# SW6124Demo_board.net
KiCad netlist of a schematic drawn in Altium Designer
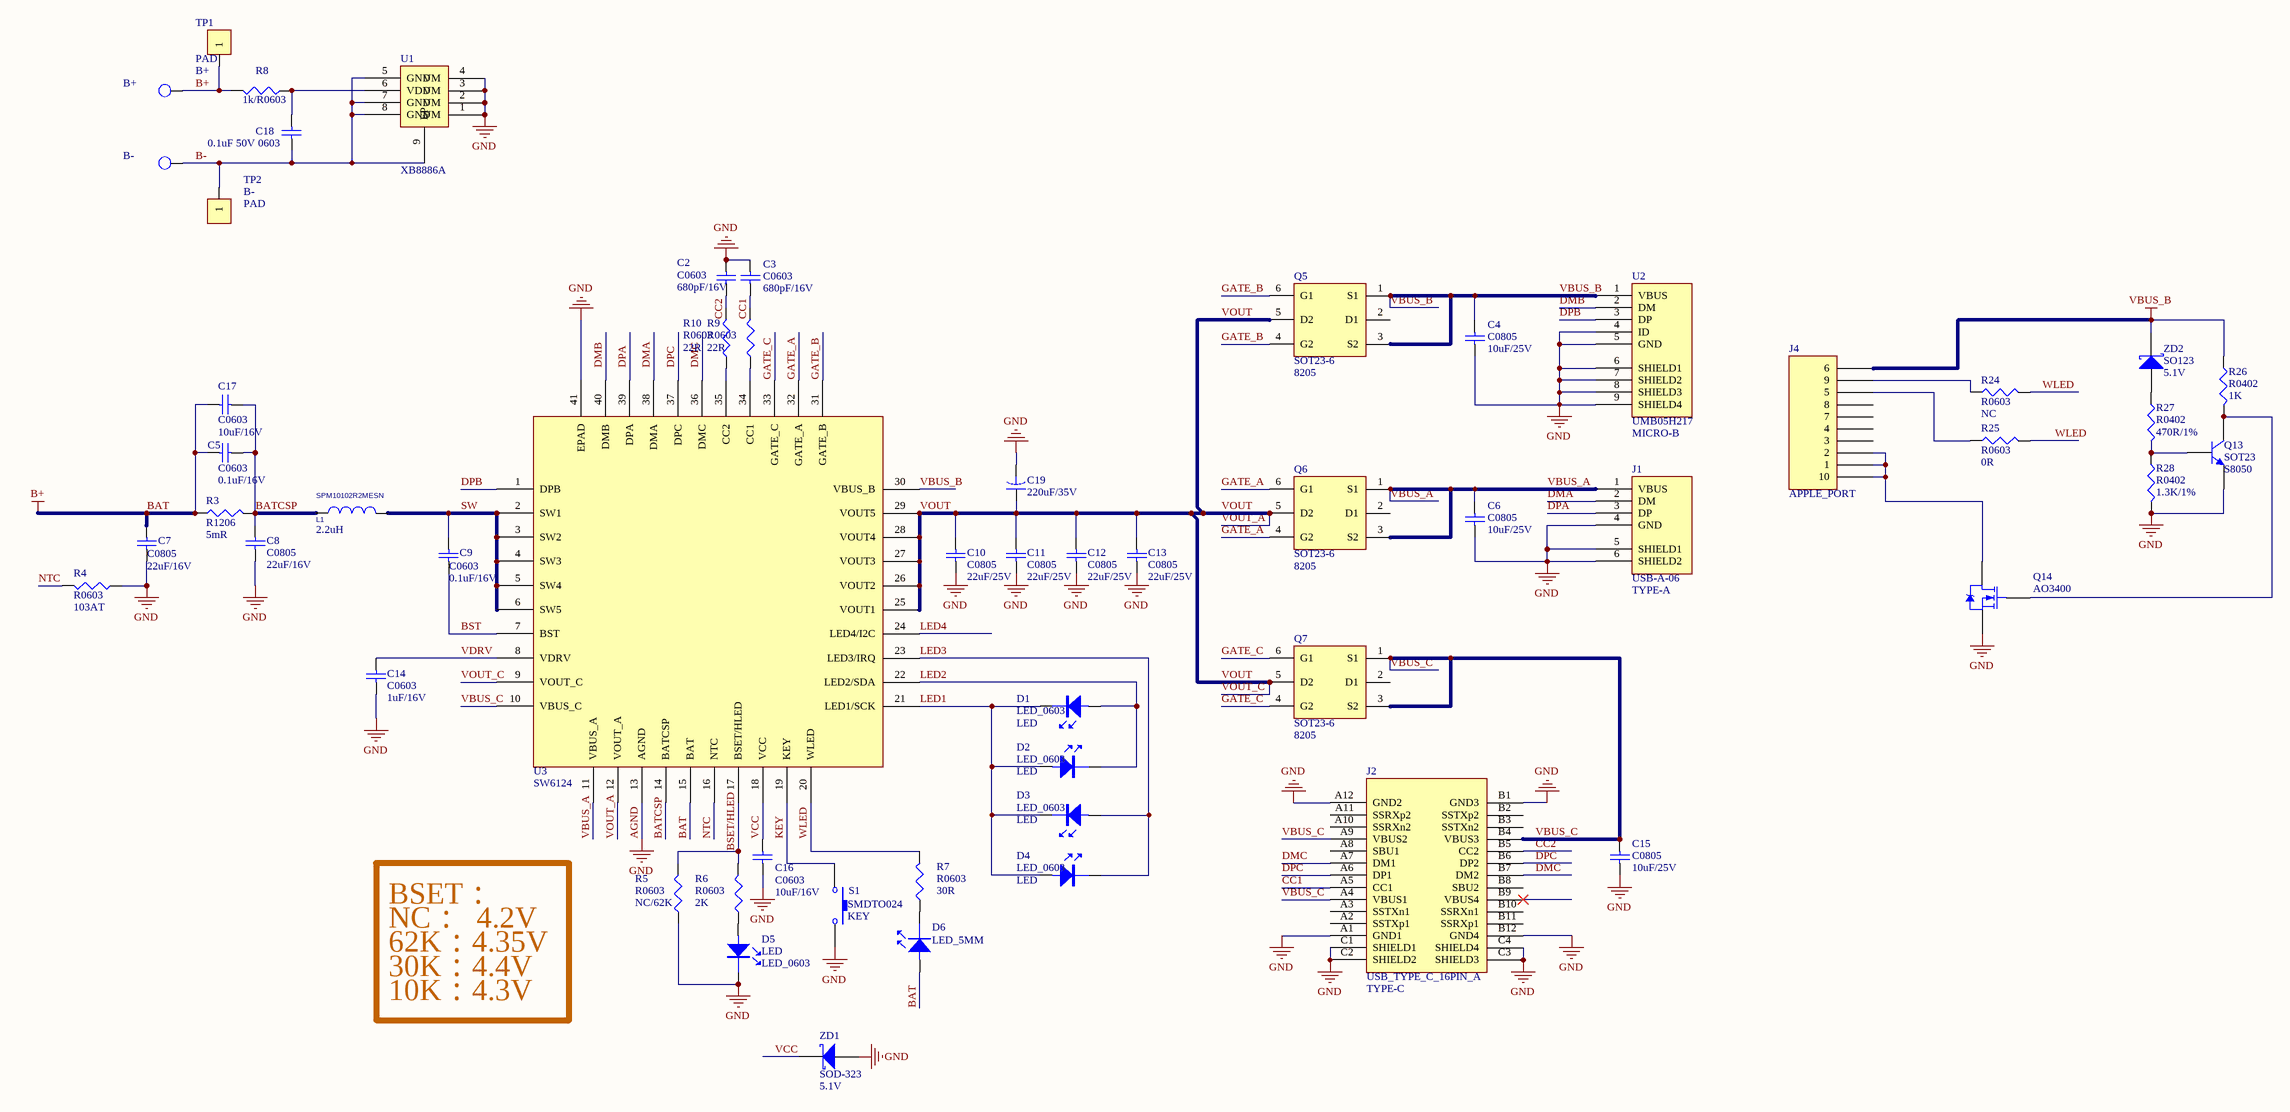
[diagram p0: SW6124Demo board.SchDoc]

(export (version "E")
  (design (tool "Eeschema 10.0.6"))
  (components
    (comp (ref "B+") (value "PDA") (footprint "PAD") (libsource (lib "ZYX") (part "PDA")))
    (comp (ref "B-") (value "PDA") (footprint "PAD") (libsource (lib "ZYX") (part "PDA")))
    (comp (ref "C2")
      (value "C0603")
      (footprint "C0603")
      (description "Capacitor")
      (fields (field (name "ALTIUM_VALUE") "680pF/16V") (field (name "PUBLISHER") "Altium Limited"))
      (libsource (lib "*") (part "CAP0603"))
    )
    (comp (ref "C3")
      (value "C0603")
      (footprint "C0603")
      (description "Capacitor")
      (fields (field (name "ALTIUM_VALUE") "680pF/16V") (field (name "PUBLISHER") "Altium Limited"))
      (libsource (lib "*") (part "CAP0603"))
    )
    (comp (ref "C4")
      (value "C0805")
      (footprint "C0805")
      (description "Capacitor")
      (fields (field (name "ALTIUM_VALUE") "10uF/25V") (field (name "PUBLISHER") "Altium Limited"))
      (libsource (lib "*") (part "CAP0603"))
    )
    (comp (ref "C5")
      (value "C0603")
      (footprint "C0603")
      (description "Capacitor")
      (fields (field (name "ALTIUM_VALUE") "0.1uF/16V") (field (name "PUBLISHER") "Altium Limited"))
      (libsource (lib "*") (part "CAP0603"))
    )
    (comp (ref "C6")
      (value "C0805")
      (footprint "C0805")
      (description "Capacitor")
      (fields (field (name "ALTIUM_VALUE") "10uF/25V") (field (name "PUBLISHER") "Altium Limited"))
      (libsource (lib "*") (part "CAP0603"))
    )
    (comp (ref "C7")
      (value "C0805")
      (footprint "C0805")
      (description "Capacitor")
      (fields (field (name "ALTIUM_VALUE") "22uF/16V") (field (name "PUBLISHER") "Altium Limited"))
      (libsource (lib "*") (part "CAP0805"))
    )
    (comp (ref "C8")
      (value "C0805")
      (footprint "C0805")
      (description "Capacitor")
      (fields (field (name "ALTIUM_VALUE") "22uF/16V") (field (name "PUBLISHER") "Altium Limited"))
      (libsource (lib "*") (part "CAP0805"))
    )
    (comp (ref "C9")
      (value "C0603")
      (footprint "C0603")
      (description "Capacitor")
      (fields (field (name "ALTIUM_VALUE") "0.1uF/16V") (field (name "PUBLISHER") "Altium Limited"))
      (libsource (lib "*") (part "CAP0603"))
    )
    (comp (ref "C10")
      (value "C0805")
      (footprint "C0805")
      (description "Capacitor")
      (fields (field (name "ALTIUM_VALUE") "22uF/25V") (field (name "PUBLISHER") "Altium Limited"))
      (libsource (lib "*") (part "CAP0805"))
    )
    (comp (ref "C11")
      (value "C0805")
      (footprint "C0805")
      (description "Capacitor")
      (fields (field (name "ALTIUM_VALUE") "22uF/25V") (field (name "PUBLISHER") "Altium Limited"))
      (libsource (lib "*") (part "CAP0805"))
    )
    (comp (ref "C12")
      (value "C0805")
      (footprint "C0805")
      (description "Capacitor")
      (fields (field (name "ALTIUM_VALUE") "22uF/25V") (field (name "PUBLISHER") "Altium Limited"))
      (libsource (lib "*") (part "CAP0805"))
    )
    (comp (ref "C13")
      (value "C0805")
      (footprint "C0805")
      (description "Capacitor")
      (fields (field (name "ALTIUM_VALUE") "22uF/25V") (field (name "PUBLISHER") "Altium Limited"))
      (libsource (lib "*") (part "CAP0805"))
    )
    (comp (ref "C14")
      (value "C0603")
      (footprint "C0603")
      (description "Capacitor")
      (fields (field (name "ALTIUM_VALUE") "1uF/16V") (field (name "PUBLISHER") "Altium Limited"))
      (libsource (lib "*") (part "CAP0603"))
    )
    (comp (ref "C15")
      (value "C0805")
      (footprint "C0805")
      (description "Capacitor")
      (fields (field (name "ALTIUM_VALUE") "10uF/25V") (field (name "PUBLISHER") "Altium Limited"))
      (libsource (lib "*") (part "CAP0603"))
    )
    (comp (ref "C16")
      (value "C0603")
      (footprint "C0603")
      (description "Capacitor")
      (fields (field (name "ALTIUM_VALUE") "10uF/16V") (field (name "PUBLISHER") "Altium Limited"))
      (libsource (lib "*") (part "CAP0603"))
    )
    (comp (ref "C17")
      (value "C0603")
      (footprint "C0603")
      (description "Capacitor")
      (fields (field (name "ALTIUM_VALUE") "10uF/16V") (field (name "PUBLISHER") "Altium Limited"))
      (libsource (lib "*") (part "CAP0603"))
    )
    (comp (ref "C18") (value "0.1uF 50V 0603") (footprint "LIB:C0402") (libsource (lib "ZYX") (part "Cap")))
    (comp (ref "C19")
      (value "220uF/35V")
      (footprint "Cap  ( E )  6.5 * 12.0  Erect")
      (description "Electroytic Capacitor, 100uF/35V, ±20%, 105℃，Φ 6.5 * 12.0 mm")
      (fields (field (name "Comment") "E - Cap") (field (name "PUBLISHER") "Altium Limited"))
      (libsource (lib "D-lib") (part "E - Cap"))
    )
    (comp (ref "D1") (value "LED") (footprint "LED_0603") (libsource (lib "*") (part "LED")))
    (comp (ref "D2") (value "LED") (footprint "LED_0603") (libsource (lib "*") (part "LED")))
    (comp (ref "D3") (value "LED") (footprint "LED_0603") (libsource (lib "*") (part "LED")))
    (comp (ref "D4") (value "LED") (footprint "LED_0603") (libsource (lib "*") (part "LED")))
    (comp (ref "D5") (value "LED") (footprint "LED_0603") (libsource (lib "*") (part "LED")))
    (comp (ref "D6")
      (value "LED_5MM")
      (footprint "LED_5MM")
      (fields (field (name "FOOTPRINF") "LED_5MM"))
      (libsource (lib "*") (part "LED"))
    )
    (comp (ref "J1")
      (value "TYPE-A")
      (footprint "USB-A-06")
      (fields (field (name "FOOTPRINF") "USB-A-06") (field (name "Comment") "TYPE-A-1"))
      (libsource (lib "*") (part "TYPE-A-1"))
    )
    (comp (ref "J2") (value "TYPE-C") (footprint "USB_TYPE_C_16PIN_A") (libsource (lib "*") (part "TYPE-C")))
    (comp (ref "J4")
      (value "APPLE_PORT")
      (footprint "Lightning")
      (libsource (lib "TEST") (part "APPLE_PORT"))
    )
    (comp (ref "L1")
      (value "SPM10102R2MESN")
      (footprint "INDUCTOR_SPM1010")
      (fields (field (name "ALTIUM_VALUE") "2.2uH"))
      (libsource (lib "*") (part "INDUCTOR"))
    )
    (comp (ref "Q5")
      (value "8205")
      (footprint "SOT23-6")
      (fields (field (name "FOOTPRINF") "SOT23-6"))
      (libsource (lib "*") (part "8205B"))
    )
    (comp (ref "Q6")
      (value "8205")
      (footprint "SOT23-6")
      (fields (field (name "FOOTPRINF") "SOT23-6"))
      (libsource (lib "*") (part "8205B"))
    )
    (comp (ref "Q7")
      (value "8205")
      (footprint "SOT23-6")
      (fields (field (name "FOOTPRINF") "SOT23-6"))
      (libsource (lib "*") (part "8205B"))
    )
    (comp (ref "Q13")
      (value "S8050")
      (footprint "SOT23")
      (description "NPN General Purpose Amplifier")
      (fields (field (name "PUBLISHER") "Altium Limited"))
      (libsource (lib "Miscellaneous Devices") (part "2N3904"))
    )
    (comp (ref "Q14")
      (value "AO3400")
      (footprint "SOT-23-3")
      (description "N-Channel Power MOSFET")
      (fields (field (name "Comment") "NMOS-2") (field (name "PUBLISHER") "Altium Limited"))
      (libsource (lib "D-lib") (part "NMOS-2"))
    )
    (comp (ref "R3")
      (value "R1206")
      (footprint "R1206")
      (description "Resistor")
      (fields (field (name "ALTIUM_VALUE") "5mR") (field (name "PUBLISHER") "Altium Limited"))
      (libsource (lib "*") (part "RES"))
    )
    (comp (ref "R4")
      (value "R0603")
      (footprint "R0603")
      (description "Resistor")
      (fields (field (name "ALTIUM_VALUE") "103AT") (field (name "PUBLISHER") "Altium Limited"))
      (libsource (lib "*") (part "RES"))
    )
    (comp (ref "R5")
      (value "R0603")
      (footprint "R0603")
      (description "Resistor")
      (fields (field (name "ALTIUM_VALUE") "NC/62K") (field (name "PUBLISHER") "Altium Limited"))
      (libsource (lib "*") (part "RES"))
    )
    (comp (ref "R6")
      (value "R0603")
      (footprint "R0603")
      (description "Resistor")
      (fields (field (name "ALTIUM_VALUE") "2K") (field (name "PUBLISHER") "Altium Limited"))
      (libsource (lib "*") (part "RES"))
    )
    (comp (ref "R7")
      (value "R0603")
      (footprint "R0603")
      (description "Resistor")
      (fields (field (name "ALTIUM_VALUE") "30R") (field (name "PUBLISHER") "Altium Limited"))
      (libsource (lib "*") (part "RES"))
    )
    (comp (ref "R8")
      (value "1k/R0603")
      (footprint "R0402")
      (description "Resistor")
      (fields (field (name "PUBLISHER") "Altium Limited"))
      (libsource (lib "*") (part "RES"))
    )
    (comp (ref "R9")
      (value "R0603")
      (footprint "R0603")
      (description "Resistor")
      (fields (field (name "ALTIUM_VALUE") "22R") (field (name "PUBLISHER") "Altium Limited"))
      (libsource (lib "*") (part "RES"))
    )
    (comp (ref "R10")
      (value "R0603")
      (footprint "R0603")
      (description "Resistor")
      (fields (field (name "ALTIUM_VALUE") "22R") (field (name "PUBLISHER") "Altium Limited"))
      (libsource (lib "*") (part "RES"))
    )
    (comp (ref "R24")
      (value "R0603")
      (footprint "R0402")
      (description "Resistor")
      (fields (field (name "ALTIUM_VALUE") "NC") (field (name "PUBLISHER") "Altium Limited"))
      (libsource (lib "*") (part "RES"))
    )
    (comp (ref "R25")
      (value "R0603")
      (footprint "R0402")
      (description "Resistor")
      (fields (field (name "ALTIUM_VALUE") "0R") (field (name "PUBLISHER") "Altium Limited"))
      (libsource (lib "*") (part "RES"))
    )
    (comp (ref "R26")
      (value "R0402")
      (footprint "R0402")
      (description "Resistor")
      (fields (field (name "ALTIUM_VALUE") "1K") (field (name "PUBLISHER") "Altium Limited"))
      (libsource (lib "Miscellaneous Devices") (part "Res3"))
    )
    (comp (ref "R27")
      (value "R0402")
      (footprint "R0402")
      (description "Resistor")
      (fields (field (name "ALTIUM_VALUE") "470R/1%") (field (name "PUBLISHER") "Altium Limited"))
      (libsource (lib "Miscellaneous Devices") (part "Res3"))
    )
    (comp (ref "R28")
      (value "R0402")
      (footprint "R0402")
      (description "Resistor")
      (fields (field (name "ALTIUM_VALUE") "1.3K/1%") (field (name "PUBLISHER") "Altium Limited"))
      (libsource (lib "Miscellaneous Devices") (part "Res3"))
    )
    (comp (ref "S1")
      (value "KEY")
      (footprint "SMDTO024")
      (fields (field (name "FOOTPRINF") "SMDTO024"))
      (libsource (lib "*") (part "SW K"))
    )
    (comp (ref "TP1") (value "B+") (footprint "PAD") (libsource (lib "*") (part "Test Point")))
    (comp (ref "TP2") (value "B-") (footprint "PAD") (libsource (lib "") (part "Test Point_1")))
    (comp (ref "U1") (value "XB8886A") (footprint "SOP-8-G") (libsource (lib "ZYX") (part "XB8089")))
    (comp (ref "U2")
      (value "MICRO-B")
      (footprint "UMB05H217")
      (fields (field (name "FOOTPRINTF") "UMB05H217") (field (name "Comment") "USB_MICRO_B"))
      (libsource (lib "*") (part "USB_MICRO_B"))
    )
    (comp (ref "U3")
      (value "SW6124")
      (footprint "QFN40_EPAD_SW6124_6X6")
      (libsource (lib "*") (part "SW6124"))
    )
    (comp (ref "ZD1")
      (value "SOD-323")
      (footprint "SOD-123")
      (description "Schottky Rectifier")
      (fields (field (name "ALTIUM_UNNAMED_1") "5.1V") (field (name "PUBLISHER") "Altium Limited"))
      (libsource (lib "Miscellaneous Devices") (part "Diode 11DQ03"))
    )
    (comp (ref "ZD2")
      (value "5.1V")
      (footprint "SO123")
      (description "Schottky Rectifier")
      (fields (field (name "PUBLISHER") "Altium Limited"))
      (libsource (lib "Miscellaneous Devices") (part "Diode 10TQ035"))
    )
  )
  (nets
    (net (code "1") (name "/B-") (class "Default")
      (node (ref "B-") (pin "0") (pintype "passive"))
      (node (ref "C18") (pin "1") (pinfunction "1_1") (pintype "passive"))
      (node (ref "TP2") (pin "1") (pinfunction "1_1") (pintype "passive"))
      (node (ref "U1") (pin "5") (pinfunction "GND_5") (pintype "passive"))
      (node (ref "U1") (pin "7") (pinfunction "GND_7") (pintype "passive"))
      (node (ref "U1") (pin "8") (pinfunction "GND_8") (pintype "passive"))
      (node (ref "U1") (pin "9") (pinfunction "EP_9") (pintype "passive"))
    )
    (net (code "2") (name "/BATCSP") (class "Default")
      (node (ref "C17") (pin "1") (pinfunction "1_1") (pintype "passive"))
      (node (ref "C5") (pin "2") (pinfunction "2_2") (pintype "passive"))
      (node (ref "C8") (pin "2") (pinfunction "2_2") (pintype "passive"))
      (node (ref "L1") (pin "1") (pinfunction "1_1") (pintype "passive"))
      (node (ref "R3") (pin "2") (pinfunction "2_2") (pintype "passive"))
      (node (ref "U3") (pin "14") (pinfunction "BATCSP_14") (pintype "passive"))
    )
    (net (code "3") (name "/BSET{slash}HLED") (class "Default")
      (node (ref "R5") (pin "2") (pinfunction "2_2") (pintype "passive"))
      (node (ref "R6") (pin "2") (pinfunction "2_2") (pintype "passive"))
      (node (ref "U3") (pin "17") (pinfunction "BSET/HLED_17") (pintype "passive"))
    )
    (net (code "4") (name "/BST") (class "Default")
      (node (ref "C9") (pin "1") (pinfunction "1_1") (pintype "passive"))
      (node (ref "U3") (pin "7") (pinfunction "BST_7") (pintype "passive"))
    )
    (net (code "5") (name "/CC1") (class "Default")
      (node (ref "J2") (pin "A5") (pinfunction "CC1_A5") (pintype "passive"))
    )
    (net (code "6") (name "/CC2") (class "Default")
      (node (ref "J2") (pin "B5") (pinfunction "CC2_B5") (pintype "passive"))
    )
    (net (code "7") (name "/DMA") (class "Default")
      (node (ref "J1") (pin "2") (pinfunction "DM_2") (pintype "passive"))
      (node (ref "U3") (pin "38") (pinfunction "DMA_38") (pintype "passive"))
    )
    (net (code "8") (name "/DMB") (class "Default")
      (node (ref "U2") (pin "2") (pinfunction "DM_2") (pintype "passive"))
      (node (ref "U3") (pin "40") (pinfunction "DMB_40") (pintype "passive"))
    )
    (net (code "9") (name "/DMC") (class "Default")
      (node (ref "J2") (pin "A7") (pinfunction "DM1_A7") (pintype "passive"))
      (node (ref "J2") (pin "B7") (pinfunction "DM2_B7") (pintype "passive"))
      (node (ref "U3") (pin "36") (pinfunction "DMC_36") (pintype "passive"))
    )
    (net (code "10") (name "/DPA") (class "Default")
      (node (ref "J1") (pin "3") (pinfunction "DP_3") (pintype "passive"))
      (node (ref "U3") (pin "39") (pinfunction "DPA_39") (pintype "passive"))
    )
    (net (code "11") (name "/DPB") (class "Default")
      (node (ref "U2") (pin "3") (pinfunction "DP_3") (pintype "passive"))
      (node (ref "U3") (pin "1") (pinfunction "DPB_1") (pintype "passive"))
    )
    (net (code "12") (name "/DPC") (class "Default")
      (node (ref "J2") (pin "A6") (pinfunction "DP1_A6") (pintype "passive"))
      (node (ref "J2") (pin "B6") (pinfunction "DP2_B6") (pintype "passive"))
      (node (ref "U3") (pin "37") (pinfunction "DPC_37") (pintype "passive"))
    )
    (net (code "13") (name "/GATE_A") (class "Default")
      (node (ref "Q6") (pin "4") (pinfunction "G2_4") (pintype "passive"))
      (node (ref "Q6") (pin "6") (pinfunction "G1_6") (pintype "passive"))
      (node (ref "U3") (pin "32") (pinfunction "GATE_A_32") (pintype "passive"))
    )
    (net (code "14") (name "/GATE_B") (class "Default")
      (node (ref "Q5") (pin "4") (pinfunction "G2_4") (pintype "passive"))
      (node (ref "Q5") (pin "6") (pinfunction "G1_6") (pintype "passive"))
      (node (ref "U3") (pin "31") (pinfunction "GATE_B_31") (pintype "passive"))
    )
    (net (code "15") (name "/GATE_C") (class "Default")
      (node (ref "Q7") (pin "4") (pinfunction "G2_4") (pintype "passive"))
      (node (ref "Q7") (pin "6") (pinfunction "G1_6") (pintype "passive"))
      (node (ref "U3") (pin "33") (pinfunction "GATE_C_33") (pintype "passive"))
    )
    (net (code "16") (name "/KEY") (class "Default")
      (node (ref "S1") (pin "1") (pinfunction "1_1") (pintype "passive"))
      (node (ref "U3") (pin "19") (pinfunction "KEY_19") (pintype "passive"))
    )
    (net (code "17") (name "/LED1") (class "Default")
      (node (ref "D1") (pin "2") (pinfunction "K_2") (pintype "passive"))
      (node (ref "D2") (pin "1") (pinfunction "A_1") (pintype "passive"))
      (node (ref "D3") (pin "2") (pinfunction "K_2") (pintype "passive"))
      (node (ref "D4") (pin "1") (pinfunction "A_1") (pintype "passive"))
      (node (ref "U3") (pin "21") (pinfunction "LED1/SCK_21") (pintype "passive"))
    )
    (net (code "18") (name "/LED2") (class "Default")
      (node (ref "D1") (pin "1") (pinfunction "A_1") (pintype "passive"))
      (node (ref "D2") (pin "2") (pinfunction "K_2") (pintype "passive"))
      (node (ref "U3") (pin "22") (pinfunction "LED2/SDA_22") (pintype "passive"))
    )
    (net (code "19") (name "/LED3") (class "Default")
      (node (ref "D3") (pin "1") (pinfunction "A_1") (pintype "passive"))
      (node (ref "D4") (pin "2") (pinfunction "K_2") (pintype "passive"))
      (node (ref "U3") (pin "23") (pinfunction "LED3/IRQ_23") (pintype "passive"))
    )
    (net (code "20") (name "/LED4") (class "Default")
      (node (ref "U3") (pin "24") (pinfunction "LED4/I2C_24") (pintype "passive"))
    )
    (net (code "21") (name "/NTC") (class "Default")
      (node (ref "R4") (pin "2") (pinfunction "2_2") (pintype "passive"))
      (node (ref "U3") (pin "16") (pinfunction "NTC_16") (pintype "passive"))
    )
    (net (code "22") (name "/SW") (class "Default")
      (node (ref "C9") (pin "2") (pinfunction "2_2") (pintype "passive"))
      (node (ref "L1") (pin "2") (pinfunction "2_2") (pintype "passive"))
      (node (ref "U3") (pin "2") (pinfunction "SW1_2") (pintype "passive"))
      (node (ref "U3") (pin "3") (pinfunction "SW2_3") (pintype "passive"))
      (node (ref "U3") (pin "4") (pinfunction "SW3_4") (pintype "passive"))
      (node (ref "U3") (pin "5") (pinfunction "SW4_5") (pintype "passive"))
      (node (ref "U3") (pin "6") (pinfunction "SW5_6") (pintype "passive"))
    )
    (net (code "23") (name "/VBUS_A") (class "Default")
      (node (ref "C6") (pin "2") (pinfunction "2_2") (pintype "passive"))
      (node (ref "J1") (pin "1") (pinfunction "VBUS_1") (pintype "passive"))
      (node (ref "Q6") (pin "1") (pinfunction "S1_1") (pintype "passive"))
      (node (ref "Q6") (pin "3") (pinfunction "S2_3") (pintype "passive"))
      (node (ref "U3") (pin "11") (pinfunction "VBUS_A_11") (pintype "passive"))
    )
    (net (code "24") (name "/VBUS_C") (class "Default")
      (node (ref "C15") (pin "2") (pinfunction "2_2") (pintype "passive"))
      (node (ref "J2") (pin "A4") (pinfunction "VBUS1_A4") (pintype "passive"))
      (node (ref "J2") (pin "A9") (pinfunction "VBUS2_A9") (pintype "passive"))
      (node (ref "J2") (pin "B4") (pinfunction "VBUS3_B4") (pintype "passive"))
      (node (ref "Q7") (pin "1") (pinfunction "S1_1") (pintype "passive"))
      (node (ref "Q7") (pin "3") (pinfunction "S2_3") (pintype "passive"))
      (node (ref "U3") (pin "10") (pinfunction "VBUS_C_10") (pintype "passive"))
    )
    (net (code "25") (name "/VCC") (class "Default")
      (node (ref "C16") (pin "2") (pinfunction "2_2") (pintype "passive"))
      (node (ref "U3") (pin "18") (pinfunction "VCC_18") (pintype "passive"))
      (node (ref "ZD1") (pin "2") (pinfunction "K_2") (pintype "passive"))
    )
    (net (code "26") (name "/VDRV") (class "Default")
      (node (ref "C14") (pin "2") (pinfunction "2_2") (pintype "passive"))
      (node (ref "U3") (pin "8") (pinfunction "VDRV_8") (pintype "passive"))
    )
    (net (code "27") (name "/VOUT") (class "Default")
      (node (ref "C10") (pin "2") (pinfunction "2_2") (pintype "passive"))
      (node (ref "C11") (pin "2") (pinfunction "2_2") (pintype "passive"))
      (node (ref "C12") (pin "2") (pinfunction "2_2") (pintype "passive"))
      (node (ref "C13") (pin "2") (pinfunction "2_2") (pintype "passive"))
      (node (ref "C19") (pin "1") (pinfunction "1_1") (pintype "passive"))
      (node (ref "Q5") (pin "5") (pinfunction "D2_5") (pintype "passive"))
      (node (ref "Q6") (pin "5") (pinfunction "D2_5") (pintype "passive"))
      (node (ref "Q7") (pin "5") (pinfunction "D2_5") (pintype "passive"))
      (node (ref "U3") (pin "12") (pinfunction "VOUT_A_12") (pintype "passive"))
      (node (ref "U3") (pin "25") (pinfunction "VOUT1_25") (pintype "passive"))
      (node (ref "U3") (pin "26") (pinfunction "VOUT2_26") (pintype "passive"))
      (node (ref "U3") (pin "27") (pinfunction "VOUT3_27") (pintype "passive"))
      (node (ref "U3") (pin "28") (pinfunction "VOUT4_28") (pintype "passive"))
      (node (ref "U3") (pin "29") (pinfunction "VOUT5_29") (pintype "passive"))
      (node (ref "U3") (pin "9") (pinfunction "VOUT_C_9") (pintype "passive"))
    )
    (net (code "28") (name "/WLED") (class "Default")
      (node (ref "R24") (pin "2") (pinfunction "2_2") (pintype "passive"))
      (node (ref "R25") (pin "2") (pinfunction "2_2") (pintype "passive"))
      (node (ref "R7") (pin "2") (pinfunction "2_2") (pintype "passive"))
      (node (ref "U3") (pin "20") (pinfunction "WLED_20") (pintype "passive"))
    )
    (net (code "29") (name "B+") (class "Default")
      (node (ref "B+") (pin "0") (pintype "passive"))
      (node (ref "C17") (pin "2") (pinfunction "2_2") (pintype "passive"))
      (node (ref "C5") (pin "1") (pinfunction "1_1") (pintype "passive"))
      (node (ref "C7") (pin "2") (pinfunction "2_2") (pintype "passive"))
      (node (ref "D6") (pin "1") (pinfunction "A_1") (pintype "passive"))
      (node (ref "R3") (pin "1") (pinfunction "1_1") (pintype "passive"))
      (node (ref "R8") (pin "2") (pinfunction "2_2") (pintype "passive"))
      (node (ref "TP1") (pin "1") (pinfunction "1_1") (pintype "passive"))
      (node (ref "U3") (pin "15") (pinfunction "BAT_15") (pintype "passive"))
    )
    (net (code "30") (name "GND") (class "Default")
      (node (ref "C10") (pin "1") (pinfunction "1_1") (pintype "passive"))
      (node (ref "C11") (pin "1") (pinfunction "1_1") (pintype "passive"))
      (node (ref "C12") (pin "1") (pinfunction "1_1") (pintype "passive"))
      (node (ref "C13") (pin "1") (pinfunction "1_1") (pintype "passive"))
      (node (ref "C14") (pin "1") (pinfunction "1_1") (pintype "passive"))
      (node (ref "C15") (pin "1") (pinfunction "1_1") (pintype "passive"))
      (node (ref "C16") (pin "1") (pinfunction "1_1") (pintype "passive"))
      (node (ref "C19") (pin "2") (pinfunction "2_2") (pintype "passive"))
      (node (ref "C2") (pin "2") (pinfunction "2_2") (pintype "passive"))
      (node (ref "C3") (pin "2") (pinfunction "2_2") (pintype "passive"))
      (node (ref "C4") (pin "1") (pinfunction "1_1") (pintype "passive"))
      (node (ref "C6") (pin "1") (pinfunction "1_1") (pintype "passive"))
      (node (ref "C7") (pin "1") (pinfunction "1_1") (pintype "passive"))
      (node (ref "C8") (pin "1") (pinfunction "1_1") (pintype "passive"))
      (node (ref "D5") (pin "2") (pinfunction "K_2") (pintype "passive"))
      (node (ref "J1") (pin "4") (pinfunction "GND_4") (pintype "passive"))
      (node (ref "J1") (pin "5") (pinfunction "SHIELD1_5") (pintype "passive"))
      (node (ref "J1") (pin "6") (pinfunction "SHIELD2_6") (pintype "passive"))
      (node (ref "J2") (pin "A1") (pinfunction "GND1_A1") (pintype "passive"))
      (node (ref "J2") (pin "A12") (pinfunction "GND2_A12") (pintype "passive"))
      (node (ref "J2") (pin "B1") (pinfunction "GND3_B1") (pintype "passive"))
      (node (ref "J2") (pin "B12") (pinfunction "GND4_B12") (pintype "passive"))
      (node (ref "J2") (pin "C1") (pinfunction "SHIELD1_C1") (pintype "passive"))
      (node (ref "J2") (pin "C2") (pinfunction "SHIELD2_C2") (pintype "passive"))
      (node (ref "J2") (pin "C3") (pinfunction "SHIELD3_C3") (pintype "passive"))
      (node (ref "J2") (pin "C4") (pinfunction "SHIELD4_C4") (pintype "passive"))
      (node (ref "Q13") (pin "2") (pinfunction "E_2") (pintype "passive"))
      (node (ref "Q14") (pin "2") (pinfunction "S_2") (pintype "passive"))
      (node (ref "R28") (pin "2") (pinfunction "2_2") (pintype "passive"))
      (node (ref "R4") (pin "1") (pinfunction "1_1") (pintype "passive"))
      (node (ref "R5") (pin "1") (pinfunction "1_1") (pintype "passive"))
      (node (ref "S1") (pin "2") (pinfunction "2_2") (pintype "passive"))
      (node (ref "U1") (pin "1") (pinfunction "VM_1") (pintype "passive"))
      (node (ref "U1") (pin "2") (pinfunction "VM_2") (pintype "passive"))
      (node (ref "U1") (pin "3") (pinfunction "VM_3") (pintype "passive"))
      (node (ref "U1") (pin "4") (pinfunction "VM_4") (pintype "passive"))
      (node (ref "U2") (pin "4") (pinfunction "ID_4") (pintype "passive"))
      (node (ref "U2") (pin "5") (pinfunction "GND_5") (pintype "passive"))
      (node (ref "U2") (pin "6") (pinfunction "SHIELD1_6") (pintype "passive"))
      (node (ref "U2") (pin "7") (pinfunction "SHIELD2_7") (pintype "passive"))
      (node (ref "U2") (pin "8") (pinfunction "SHIELD3_8") (pintype "passive"))
      (node (ref "U2") (pin "9") (pinfunction "SHIELD4_9") (pintype "passive"))
      (node (ref "U3") (pin "13") (pinfunction "AGND_13") (pintype "passive"))
      (node (ref "U3") (pin "41") (pinfunction "EPAD_41") (pintype "passive"))
      (node (ref "ZD1") (pin "1") (pinfunction "A_1") (pintype "passive"))
    )
    (net (code "31") (name "Net-(C2-Pad1)") (class "Default")
      (node (ref "C2") (pin "1") (pinfunction "1_1") (pintype "passive"))
      (node (ref "R10") (pin "2") (pinfunction "2_2") (pintype "passive"))
    )
    (net (code "32") (name "Net-(C3-Pad1)") (class "Default")
      (node (ref "C3") (pin "1") (pinfunction "1_1") (pintype "passive"))
      (node (ref "R9") (pin "2") (pinfunction "2_2") (pintype "passive"))
    )
    (net (code "33") (name "Net-(D5-A)") (class "Default")
      (node (ref "D5") (pin "1") (pinfunction "A_1") (pintype "passive"))
      (node (ref "R6") (pin "1") (pinfunction "1_1") (pintype "passive"))
    )
    (net (code "34") (name "Net-(D6-K)") (class "Default")
      (node (ref "D6") (pin "2") (pinfunction "K_2") (pintype "passive"))
      (node (ref "R7") (pin "1") (pinfunction "1_1") (pintype "passive"))
    )
    (net (code "35") (name "Net-(J4-Pad5)") (class "Default")
      (node (ref "J4") (pin "5") (pinfunction "5_5") (pintype "passive"))
      (node (ref "R25") (pin "1") (pinfunction "1_1") (pintype "passive"))
    )
    (net (code "36") (name "Net-(J4-Pad9)") (class "Default")
      (node (ref "J4") (pin "9") (pinfunction "9_9") (pintype "passive"))
      (node (ref "R24") (pin "1") (pinfunction "1_1") (pintype "passive"))
    )
    (net (code "37") (name "Net-(Q13-B)") (class "Default")
      (node (ref "Q13") (pin "1") (pinfunction "B_1") (pintype "passive"))
      (node (ref "R27") (pin "2") (pinfunction "2_2") (pintype "passive"))
      (node (ref "R28") (pin "1") (pinfunction "1_1") (pintype "passive"))
    )
    (net (code "38") (name "Net-(Q13-C)") (class "Default")
      (node (ref "Q13") (pin "3") (pinfunction "C_3") (pintype "passive"))
      (node (ref "Q14") (pin "1") (pinfunction "G_1") (pintype "passive"))
      (node (ref "R26") (pin "2") (pinfunction "2_2") (pintype "passive"))
    )
    (net (code "39") (name "Net-(Q14-D)") (class "Default")
      (node (ref "J4") (pin "1") (pinfunction "1_1") (pintype "passive"))
      (node (ref "J4") (pin "10") (pinfunction "10_10") (pintype "passive"))
      (node (ref "J4") (pin "2") (pinfunction "2_2") (pintype "passive"))
      (node (ref "Q14") (pin "3") (pinfunction "D_3") (pintype "passive"))
    )
    (net (code "40") (name "Net-(U1-VDD)") (class "Default")
      (node (ref "C18") (pin "0") (pinfunction "0_0") (pintype "passive"))
      (node (ref "R8") (pin "1") (pinfunction "1_1") (pintype "passive"))
      (node (ref "U1") (pin "6") (pinfunction "VDD_6") (pintype "passive"))
    )
    (net (code "41") (name "Net-(U3-CC1)") (class "Default")
      (node (ref "R9") (pin "1") (pinfunction "1_1") (pintype "passive"))
      (node (ref "U3") (pin "34") (pinfunction "CC1_34") (pintype "passive"))
    )
    (net (code "42") (name "Net-(U3-CC2)") (class "Default")
      (node (ref "R10") (pin "1") (pinfunction "1_1") (pintype "passive"))
      (node (ref "U3") (pin "35") (pinfunction "CC2_35") (pintype "passive"))
    )
    (net (code "43") (name "Net-(ZD2-A)") (class "Default")
      (node (ref "R27") (pin "1") (pinfunction "1_1") (pintype "passive"))
      (node (ref "ZD2") (pin "3") (pinfunction "A_3") (pintype "passive"))
    )
    (net (code "44") (name "VBUS_B") (class "Default")
      (node (ref "C4") (pin "2") (pinfunction "2_2") (pintype "passive"))
      (node (ref "J4") (pin "6") (pinfunction "6_6") (pintype "passive"))
      (node (ref "Q5") (pin "1") (pinfunction "S1_1") (pintype "passive"))
      (node (ref "Q5") (pin "3") (pinfunction "S2_3") (pintype "passive"))
      (node (ref "R26") (pin "1") (pinfunction "1_1") (pintype "passive"))
      (node (ref "U2") (pin "1") (pinfunction "VBUS_1") (pintype "passive"))
      (node (ref "U3") (pin "30") (pinfunction "VBUS_B_30") (pintype "passive"))
      (node (ref "ZD2") (pin "1") (pinfunction "K_1") (pintype "passive"))
    )
    (net (code "45") (name "unconnected-(J2-SBU1-PadA8)") (class "Default")
      (node (ref "J2") (pin "A8") (pinfunction "SBU1_A8") (pintype "passive"))
    )
    (net (code "46") (name "unconnected-(J2-SBU2-PadB8)") (class "Default")
      (node (ref "J2") (pin "B8") (pinfunction "SBU2_B8") (pintype "passive"))
    )
    (net (code "47") (name "unconnected-(J2-SSRXn1-PadB10)") (class "Default")
      (node (ref "J2") (pin "B10") (pinfunction "SSRXn1_B10") (pintype "passive"))
    )
    (net (code "48") (name "unconnected-(J2-SSRXn2-PadA10)") (class "Default")
      (node (ref "J2") (pin "A10") (pinfunction "SSRXn2_A10") (pintype "passive"))
    )
    (net (code "49") (name "unconnected-(J2-SSRXp1-PadB11)") (class "Default")
      (node (ref "J2") (pin "B11") (pinfunction "SSRXp1_B11") (pintype "passive"))
    )
    (net (code "50") (name "unconnected-(J2-SSRXp2-PadA11)") (class "Default")
      (node (ref "J2") (pin "A11") (pinfunction "SSRXp2_A11") (pintype "passive"))
    )
    (net (code "51") (name "unconnected-(J2-SSTXn1-PadA3)") (class "Default")
      (node (ref "J2") (pin "A3") (pinfunction "SSTXn1_A3") (pintype "passive"))
    )
    (net (code "52") (name "unconnected-(J2-SSTXn2-PadB3)") (class "Default")
      (node (ref "J2") (pin "B3") (pinfunction "SSTXn2_B3") (pintype "passive"))
    )
    (net (code "53") (name "unconnected-(J2-SSTXp1-PadA2)") (class "Default")
      (node (ref "J2") (pin "A2") (pinfunction "SSTXp1_A2") (pintype "passive"))
    )
    (net (code "54") (name "unconnected-(J2-SSTXp2-PadB2)") (class "Default")
      (node (ref "J2") (pin "B2") (pinfunction "SSTXp2_B2") (pintype "passive"))
    )
    (net (code "55") (name "unconnected-(J2-VBUS4-PadB9)") (class "Default")
      (node (ref "J2") (pin "B9") (pinfunction "VBUS4_B9") (pintype "passive+no_connect"))
    )
    (net (code "56") (name "unconnected-(J4-Pad3)") (class "Default")
      (node (ref "J4") (pin "3") (pinfunction "3_3") (pintype "passive"))
    )
    (net (code "57") (name "unconnected-(J4-Pad4)") (class "Default")
      (node (ref "J4") (pin "4") (pinfunction "4_4") (pintype "passive"))
    )
    (net (code "58") (name "unconnected-(J4-Pad7)") (class "Default")
      (node (ref "J4") (pin "7") (pinfunction "7_7") (pintype "passive"))
    )
    (net (code "59") (name "unconnected-(J4-Pad8)") (class "Default")
      (node (ref "J4") (pin "8") (pinfunction "8_8") (pintype "passive"))
    )
    (net (code "60") (name "unconnected-(Q5-D1-Pad2)") (class "Default")
      (node (ref "Q5") (pin "2") (pinfunction "D1_2") (pintype "passive"))
    )
    (net (code "61") (name "unconnected-(Q6-D1-Pad2)") (class "Default")
      (node (ref "Q6") (pin "2") (pinfunction "D1_2") (pintype "passive"))
    )
    (net (code "62") (name "unconnected-(Q7-D1-Pad2)") (class "Default")
      (node (ref "Q7") (pin "2") (pinfunction "D1_2") (pintype "passive"))
    )
  )
)
